# Connectors.net
KiCad netlist of a schematic drawn in Altium Designer
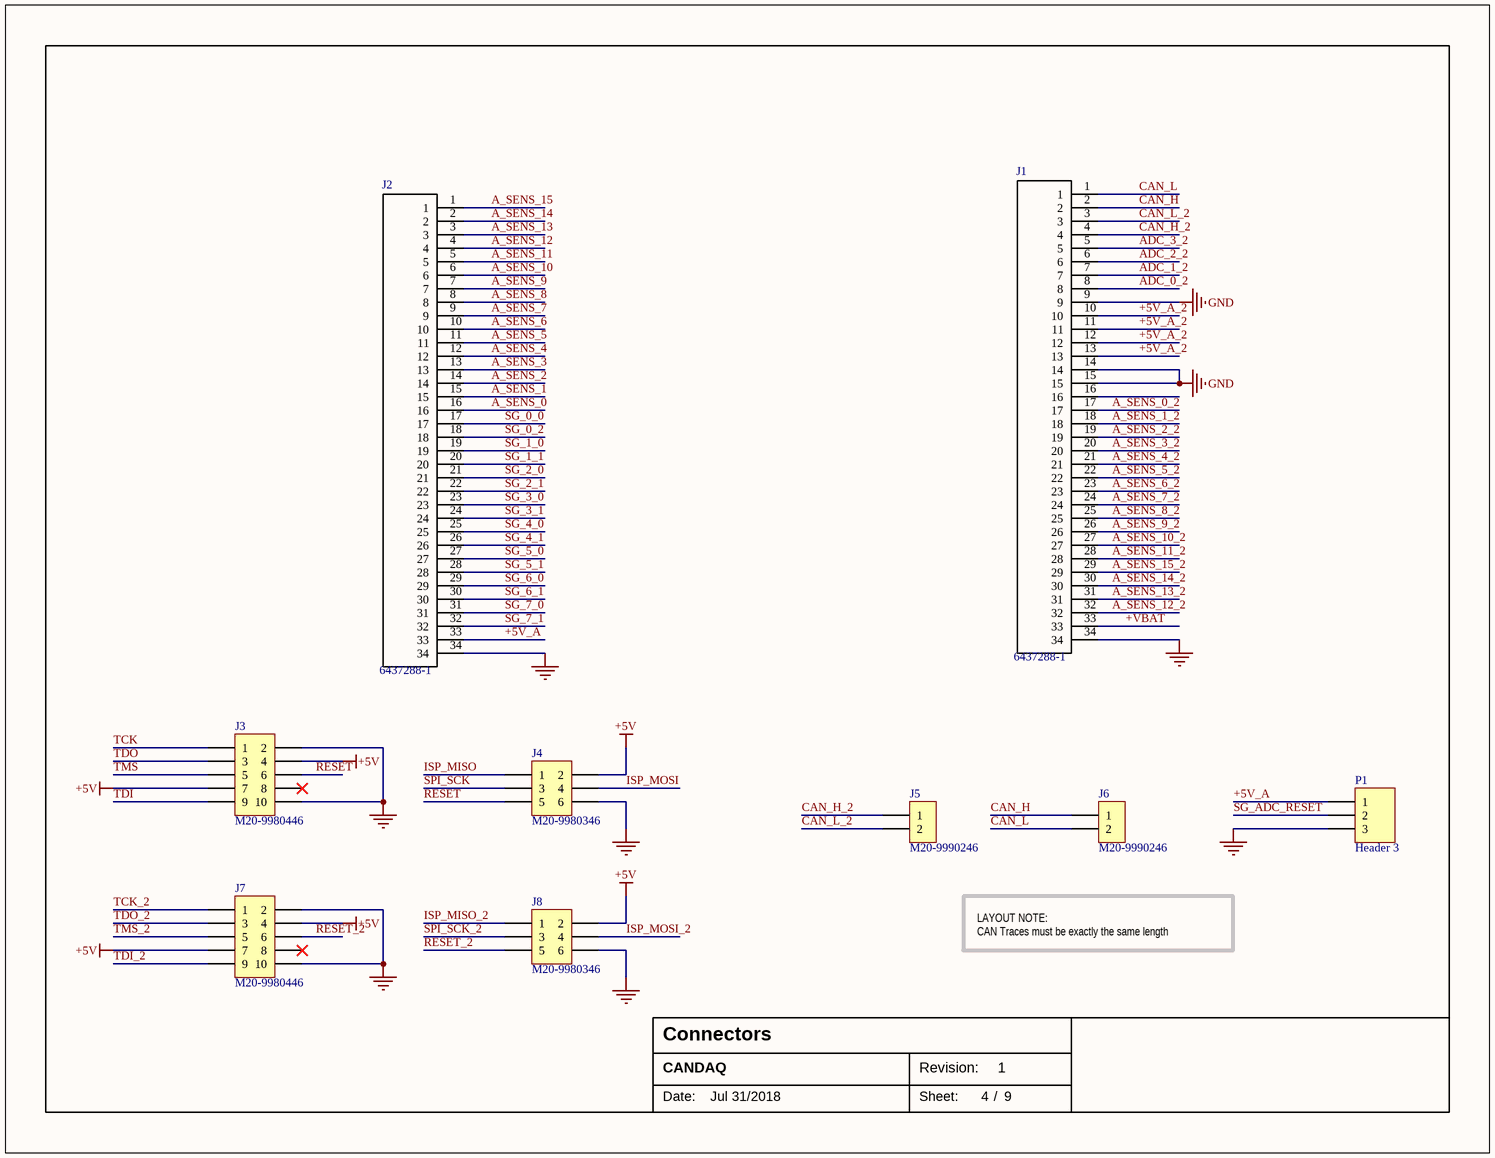
[diagram p0: Connectors.SchDoc]

(export (version "E")
  (design (tool "Eeschema 10.0.6"))
  (components
    (comp (ref "J1")
      (value "6437288-1")
      (footprint "TE_6437288-1")
      (description "34 Position 4 Row Right Angle Receptacle Through Hole Super Seal Cap Assy")
      (fields (field (name "DIGI-KEY_PART_NUMBER") "A124384-ND") (field (name "MF") "TE Connectivity"))
      (libsource (lib "6437288-1") (part "6437288-1"))
    )
    (comp (ref "J2")
      (value "6437288-1")
      (footprint "TE_6437288-1")
      (description "34 Position 4 Row Right Angle Receptacle Through Hole Super Seal Cap Assy")
      (fields (field (name "DIGI-KEY_PART_NUMBER") "A124384-ND") (field (name "MF") "TE Connectivity"))
      (libsource (lib "6437288-1") (part "6437288-1"))
    )
    (comp (ref "J3")
      (value "M20-9980446")
      (footprint "M20-9980446")
      (description "2.54mm Header 2x4-Pin")
      (libsource (lib "CANDAQ") (part "M20-9980446"))
    )
    (comp (ref "J4")
      (value "M20-9980346")
      (footprint "M20-9980346")
      (description "2.54mm Header 2x3-Pin")
      (libsource (lib "CANDAQ") (part "M20-9980346"))
    )
    (comp (ref "J5")
      (value "M20-9990246")
      (footprint "M20-9990246")
      (description "2.54mm Header 1x2-Pin")
      (libsource (lib "PDU-UV17") (part "M20-9990246"))
    )
    (comp (ref "J6")
      (value "M20-9990246")
      (footprint "M20-9990246")
      (description "2.54mm Header 1x2-Pin")
      (libsource (lib "PDU-UV17") (part "M20-9990246"))
    )
    (comp (ref "J7")
      (value "M20-9980446")
      (footprint "M20-9980446")
      (description "2.54mm Header 2x4-Pin")
      (libsource (lib "CANDAQ") (part "M20-9980446"))
    )
    (comp (ref "J8")
      (value "M20-9980346")
      (footprint "M20-9980346")
      (description "2.54mm Header 2x3-Pin")
      (libsource (lib "CANDAQ") (part "M20-9980346"))
    )
    (comp (ref "P1")
      (value "Header 3")
      (footprint "HDR1X3")
      (description "Header, 3-Pin")
      (fields (field (name "PUBLISHER") "Altium Limited"))
      (libsource (lib "Miscellaneous Connectors") (part "Header 3"))
    )
  )
  (nets
    (net (code "1") (name "+5V") (class "Default")
      (node (ref "J3") (pin "4") (pinfunction "4_4") (pintype "passive"))
      (node (ref "J3") (pin "7") (pinfunction "7_7") (pintype "passive"))
      (node (ref "J4") (pin "2") (pinfunction "2_2") (pintype "passive"))
      (node (ref "J7") (pin "4") (pinfunction "4_4") (pintype "passive"))
      (node (ref "J7") (pin "7") (pinfunction "7_7") (pintype "passive"))
      (node (ref "J8") (pin "2") (pinfunction "2_2") (pintype "passive"))
    )
    (net (code "2") (name "/+5V_A") (class "Default")
      (node (ref "J2") (pin "33") (pinfunction "33_33") (pintype "passive"))
      (node (ref "P1") (pin "1") (pinfunction "1_1") (pintype "passive"))
    )
    (net (code "3") (name "/+5V_A_2") (class "Default")
      (node (ref "J1") (pin "10") (pinfunction "10_10") (pintype "passive"))
      (node (ref "J1") (pin "11") (pinfunction "11_11") (pintype "passive"))
      (node (ref "J1") (pin "12") (pinfunction "12_12") (pintype "passive"))
      (node (ref "J1") (pin "13") (pinfunction "13_13") (pintype "passive"))
    )
    (net (code "4") (name "/+VBAT") (class "Default")
      (node (ref "J1") (pin "33") (pinfunction "33_33") (pintype "passive"))
    )
    (net (code "5") (name "/ADC_0_2") (class "Default")
      (node (ref "J1") (pin "8") (pinfunction "8_8") (pintype "passive"))
    )
    (net (code "6") (name "/ADC_1_2") (class "Default")
      (node (ref "J1") (pin "7") (pinfunction "7_7") (pintype "passive"))
    )
    (net (code "7") (name "/ADC_2_2") (class "Default")
      (node (ref "J1") (pin "6") (pinfunction "6_6") (pintype "passive"))
    )
    (net (code "8") (name "/ADC_3_2") (class "Default")
      (node (ref "J1") (pin "5") (pinfunction "5_5") (pintype "passive"))
    )
    (net (code "9") (name "/A_SENS_0") (class "Default")
      (node (ref "J2") (pin "16") (pinfunction "16_16") (pintype "passive"))
    )
    (net (code "10") (name "/A_SENS_0_2") (class "Default")
      (node (ref "J1") (pin "17") (pinfunction "17_17") (pintype "passive"))
    )
    (net (code "11") (name "/A_SENS_1") (class "Default")
      (node (ref "J2") (pin "15") (pinfunction "15_15") (pintype "passive"))
    )
    (net (code "12") (name "/A_SENS_1_2") (class "Default")
      (node (ref "J1") (pin "18") (pinfunction "18_18") (pintype "passive"))
    )
    (net (code "13") (name "/A_SENS_2") (class "Default")
      (node (ref "J2") (pin "14") (pinfunction "14_14") (pintype "passive"))
    )
    (net (code "14") (name "/A_SENS_2_2") (class "Default")
      (node (ref "J1") (pin "19") (pinfunction "19_19") (pintype "passive"))
    )
    (net (code "15") (name "/A_SENS_3") (class "Default")
      (node (ref "J2") (pin "13") (pinfunction "13_13") (pintype "passive"))
    )
    (net (code "16") (name "/A_SENS_3_2") (class "Default")
      (node (ref "J1") (pin "20") (pinfunction "20_20") (pintype "passive"))
    )
    (net (code "17") (name "/A_SENS_4") (class "Default")
      (node (ref "J2") (pin "12") (pinfunction "12_12") (pintype "passive"))
    )
    (net (code "18") (name "/A_SENS_4_2") (class "Default")
      (node (ref "J1") (pin "21") (pinfunction "21_21") (pintype "passive"))
    )
    (net (code "19") (name "/A_SENS_5") (class "Default")
      (node (ref "J2") (pin "11") (pinfunction "11_11") (pintype "passive"))
    )
    (net (code "20") (name "/A_SENS_5_2") (class "Default")
      (node (ref "J1") (pin "22") (pinfunction "22_22") (pintype "passive"))
    )
    (net (code "21") (name "/A_SENS_6") (class "Default")
      (node (ref "J2") (pin "10") (pinfunction "10_10") (pintype "passive"))
    )
    (net (code "22") (name "/A_SENS_6_2") (class "Default")
      (node (ref "J1") (pin "23") (pinfunction "23_23") (pintype "passive"))
    )
    (net (code "23") (name "/A_SENS_7") (class "Default")
      (node (ref "J2") (pin "9") (pinfunction "9_9") (pintype "passive"))
    )
    (net (code "24") (name "/A_SENS_7_2") (class "Default")
      (node (ref "J1") (pin "24") (pinfunction "24_24") (pintype "passive"))
    )
    (net (code "25") (name "/A_SENS_8") (class "Default")
      (node (ref "J2") (pin "8") (pinfunction "8_8") (pintype "passive"))
    )
    (net (code "26") (name "/A_SENS_8_2") (class "Default")
      (node (ref "J1") (pin "25") (pinfunction "25_25") (pintype "passive"))
    )
    (net (code "27") (name "/A_SENS_9") (class "Default")
      (node (ref "J2") (pin "7") (pinfunction "7_7") (pintype "passive"))
    )
    (net (code "28") (name "/A_SENS_9_2") (class "Default")
      (node (ref "J1") (pin "26") (pinfunction "26_26") (pintype "passive"))
    )
    (net (code "29") (name "/A_SENS_10") (class "Default")
      (node (ref "J2") (pin "6") (pinfunction "6_6") (pintype "passive"))
    )
    (net (code "30") (name "/A_SENS_10_2") (class "Default")
      (node (ref "J1") (pin "27") (pinfunction "27_27") (pintype "passive"))
    )
    (net (code "31") (name "/A_SENS_11") (class "Default")
      (node (ref "J2") (pin "5") (pinfunction "5_5") (pintype "passive"))
    )
    (net (code "32") (name "/A_SENS_11_2") (class "Default")
      (node (ref "J1") (pin "28") (pinfunction "28_28") (pintype "passive"))
    )
    (net (code "33") (name "/A_SENS_12") (class "Default")
      (node (ref "J2") (pin "4") (pinfunction "4_4") (pintype "passive"))
    )
    (net (code "34") (name "/A_SENS_12_2") (class "Default")
      (node (ref "J1") (pin "32") (pinfunction "32_32") (pintype "passive"))
    )
    (net (code "35") (name "/A_SENS_13") (class "Default")
      (node (ref "J2") (pin "3") (pinfunction "3_3") (pintype "passive"))
    )
    (net (code "36") (name "/A_SENS_13_2") (class "Default")
      (node (ref "J1") (pin "31") (pinfunction "31_31") (pintype "passive"))
    )
    (net (code "37") (name "/A_SENS_14") (class "Default")
      (node (ref "J2") (pin "2") (pinfunction "2_2") (pintype "passive"))
    )
    (net (code "38") (name "/A_SENS_14_2") (class "Default")
      (node (ref "J1") (pin "30") (pinfunction "30_30") (pintype "passive"))
    )
    (net (code "39") (name "/A_SENS_15") (class "Default")
      (node (ref "J2") (pin "1") (pinfunction "1_1") (pintype "passive"))
    )
    (net (code "40") (name "/A_SENS_15_2") (class "Default")
      (node (ref "J1") (pin "29") (pinfunction "29_29") (pintype "passive"))
    )
    (net (code "41") (name "/CAN_H") (class "Default")
      (node (ref "J1") (pin "2") (pinfunction "2_2") (pintype "passive"))
      (node (ref "J6") (pin "1") (pinfunction "1_1") (pintype "passive"))
    )
    (net (code "42") (name "/CAN_H_2") (class "Default")
      (node (ref "J1") (pin "4") (pinfunction "4_4") (pintype "passive"))
      (node (ref "J5") (pin "1") (pinfunction "1_1") (pintype "passive"))
    )
    (net (code "43") (name "/CAN_L") (class "Default")
      (node (ref "J1") (pin "1") (pinfunction "1_1") (pintype "passive"))
      (node (ref "J6") (pin "2") (pinfunction "2_2") (pintype "passive"))
    )
    (net (code "44") (name "/CAN_L_2") (class "Default")
      (node (ref "J1") (pin "3") (pinfunction "3_3") (pintype "passive"))
      (node (ref "J5") (pin "2") (pinfunction "2_2") (pintype "passive"))
    )
    (net (code "45") (name "/ISP_MISO") (class "Default")
      (node (ref "J4") (pin "1") (pinfunction "1_1") (pintype "passive"))
    )
    (net (code "46") (name "/ISP_MISO_2") (class "Default")
      (node (ref "J8") (pin "1") (pinfunction "1_1") (pintype "passive"))
    )
    (net (code "47") (name "/ISP_MOSI") (class "Default")
      (node (ref "J4") (pin "4") (pinfunction "4_4") (pintype "passive"))
    )
    (net (code "48") (name "/ISP_MOSI_2") (class "Default")
      (node (ref "J8") (pin "4") (pinfunction "4_4") (pintype "passive"))
    )
    (net (code "49") (name "/RESET") (class "Default")
      (node (ref "J3") (pin "6") (pinfunction "6_6") (pintype "passive"))
      (node (ref "J4") (pin "5") (pinfunction "5_5") (pintype "passive"))
    )
    (net (code "50") (name "/RESET_2") (class "Default")
      (node (ref "J7") (pin "6") (pinfunction "6_6") (pintype "passive"))
      (node (ref "J8") (pin "5") (pinfunction "5_5") (pintype "passive"))
    )
    (net (code "51") (name "/SG_0_0") (class "Default")
      (node (ref "J2") (pin "17") (pinfunction "17_17") (pintype "passive"))
    )
    (net (code "52") (name "/SG_0_2") (class "Default")
      (node (ref "J2") (pin "18") (pinfunction "18_18") (pintype "passive"))
    )
    (net (code "53") (name "/SG_1_0") (class "Default")
      (node (ref "J2") (pin "19") (pinfunction "19_19") (pintype "passive"))
    )
    (net (code "54") (name "/SG_1_1") (class "Default")
      (node (ref "J2") (pin "20") (pinfunction "20_20") (pintype "passive"))
    )
    (net (code "55") (name "/SG_2_0") (class "Default")
      (node (ref "J2") (pin "21") (pinfunction "21_21") (pintype "passive"))
    )
    (net (code "56") (name "/SG_2_1") (class "Default")
      (node (ref "J2") (pin "22") (pinfunction "22_22") (pintype "passive"))
    )
    (net (code "57") (name "/SG_3_0") (class "Default")
      (node (ref "J2") (pin "23") (pinfunction "23_23") (pintype "passive"))
    )
    (net (code "58") (name "/SG_3_1") (class "Default")
      (node (ref "J2") (pin "24") (pinfunction "24_24") (pintype "passive"))
    )
    (net (code "59") (name "/SG_4_0") (class "Default")
      (node (ref "J2") (pin "25") (pinfunction "25_25") (pintype "passive"))
    )
    (net (code "60") (name "/SG_4_1") (class "Default")
      (node (ref "J2") (pin "26") (pinfunction "26_26") (pintype "passive"))
    )
    (net (code "61") (name "/SG_5_0") (class "Default")
      (node (ref "J2") (pin "27") (pinfunction "27_27") (pintype "passive"))
    )
    (net (code "62") (name "/SG_5_1") (class "Default")
      (node (ref "J2") (pin "28") (pinfunction "28_28") (pintype "passive"))
    )
    (net (code "63") (name "/SG_6_0") (class "Default")
      (node (ref "J2") (pin "29") (pinfunction "29_29") (pintype "passive"))
    )
    (net (code "64") (name "/SG_6_1") (class "Default")
      (node (ref "J2") (pin "30") (pinfunction "30_30") (pintype "passive"))
    )
    (net (code "65") (name "/SG_7_0") (class "Default")
      (node (ref "J2") (pin "31") (pinfunction "31_31") (pintype "passive"))
    )
    (net (code "66") (name "/SG_7_1") (class "Default")
      (node (ref "J2") (pin "32") (pinfunction "32_32") (pintype "passive"))
    )
    (net (code "67") (name "/SG_ADC~{_RESET}") (class "Default")
      (node (ref "P1") (pin "2") (pinfunction "2_2") (pintype "passive"))
    )
    (net (code "68") (name "/SPI_SCK") (class "Default")
      (node (ref "J4") (pin "3") (pinfunction "3_3") (pintype "passive"))
    )
    (net (code "69") (name "/SPI_SCK_2") (class "Default")
      (node (ref "J8") (pin "3") (pinfunction "3_3") (pintype "passive"))
    )
    (net (code "70") (name "/TCK") (class "Default")
      (node (ref "J3") (pin "1") (pinfunction "1_1") (pintype "passive"))
    )
    (net (code "71") (name "/TCK_2") (class "Default")
      (node (ref "J7") (pin "1") (pinfunction "1_1") (pintype "passive"))
    )
    (net (code "72") (name "/TDI") (class "Default")
      (node (ref "J3") (pin "9") (pinfunction "9_9") (pintype "passive"))
    )
    (net (code "73") (name "/TDI_2") (class "Default")
      (node (ref "J7") (pin "9") (pinfunction "9_9") (pintype "passive"))
    )
    (net (code "74") (name "/TDO") (class "Default")
      (node (ref "J3") (pin "3") (pinfunction "3_3") (pintype "passive"))
    )
    (net (code "75") (name "/TDO_2") (class "Default")
      (node (ref "J7") (pin "3") (pinfunction "3_3") (pintype "passive"))
    )
    (net (code "76") (name "/TMS") (class "Default")
      (node (ref "J3") (pin "5") (pinfunction "5_5") (pintype "passive"))
    )
    (net (code "77") (name "/TMS_2") (class "Default")
      (node (ref "J7") (pin "5") (pinfunction "5_5") (pintype "passive"))
    )
    (net (code "78") (name "GND") (class "Default")
      (node (ref "J1") (pin "14") (pinfunction "14_14") (pintype "passive"))
      (node (ref "J1") (pin "15") (pinfunction "15_15") (pintype "passive"))
      (node (ref "J1") (pin "34") (pinfunction "34_34") (pintype "passive"))
      (node (ref "J1") (pin "9") (pinfunction "9_9") (pintype "passive"))
      (node (ref "J2") (pin "34") (pinfunction "34_34") (pintype "passive"))
      (node (ref "J3") (pin "10") (pinfunction "10_10") (pintype "passive"))
      (node (ref "J3") (pin "2") (pinfunction "2_2") (pintype "passive"))
      (node (ref "J4") (pin "6") (pinfunction "6_6") (pintype "passive"))
      (node (ref "J7") (pin "10") (pinfunction "10_10") (pintype "passive"))
      (node (ref "J7") (pin "2") (pinfunction "2_2") (pintype "passive"))
      (node (ref "J8") (pin "6") (pinfunction "6_6") (pintype "passive"))
      (node (ref "P1") (pin "3") (pinfunction "3_3") (pintype "passive"))
    )
    (net (code "79") (name "unconnected-(J1-Pad16)") (class "Default")
      (node (ref "J1") (pin "16") (pinfunction "16_16") (pintype "passive"))
    )
    (net (code "80") (name "unconnected-(J3-Pad8)") (class "Default")
      (node (ref "J3") (pin "8") (pinfunction "8_8") (pintype "passive+no_connect"))
    )
    (net (code "81") (name "unconnected-(J7-Pad8)") (class "Default")
      (node (ref "J7") (pin "8") (pinfunction "8_8") (pintype "passive+no_connect"))
    )
  )
)
